# SCH_mgts_main_board_2026-06-15.net
KiCad netlist of a schematic drawn in EasyEDA
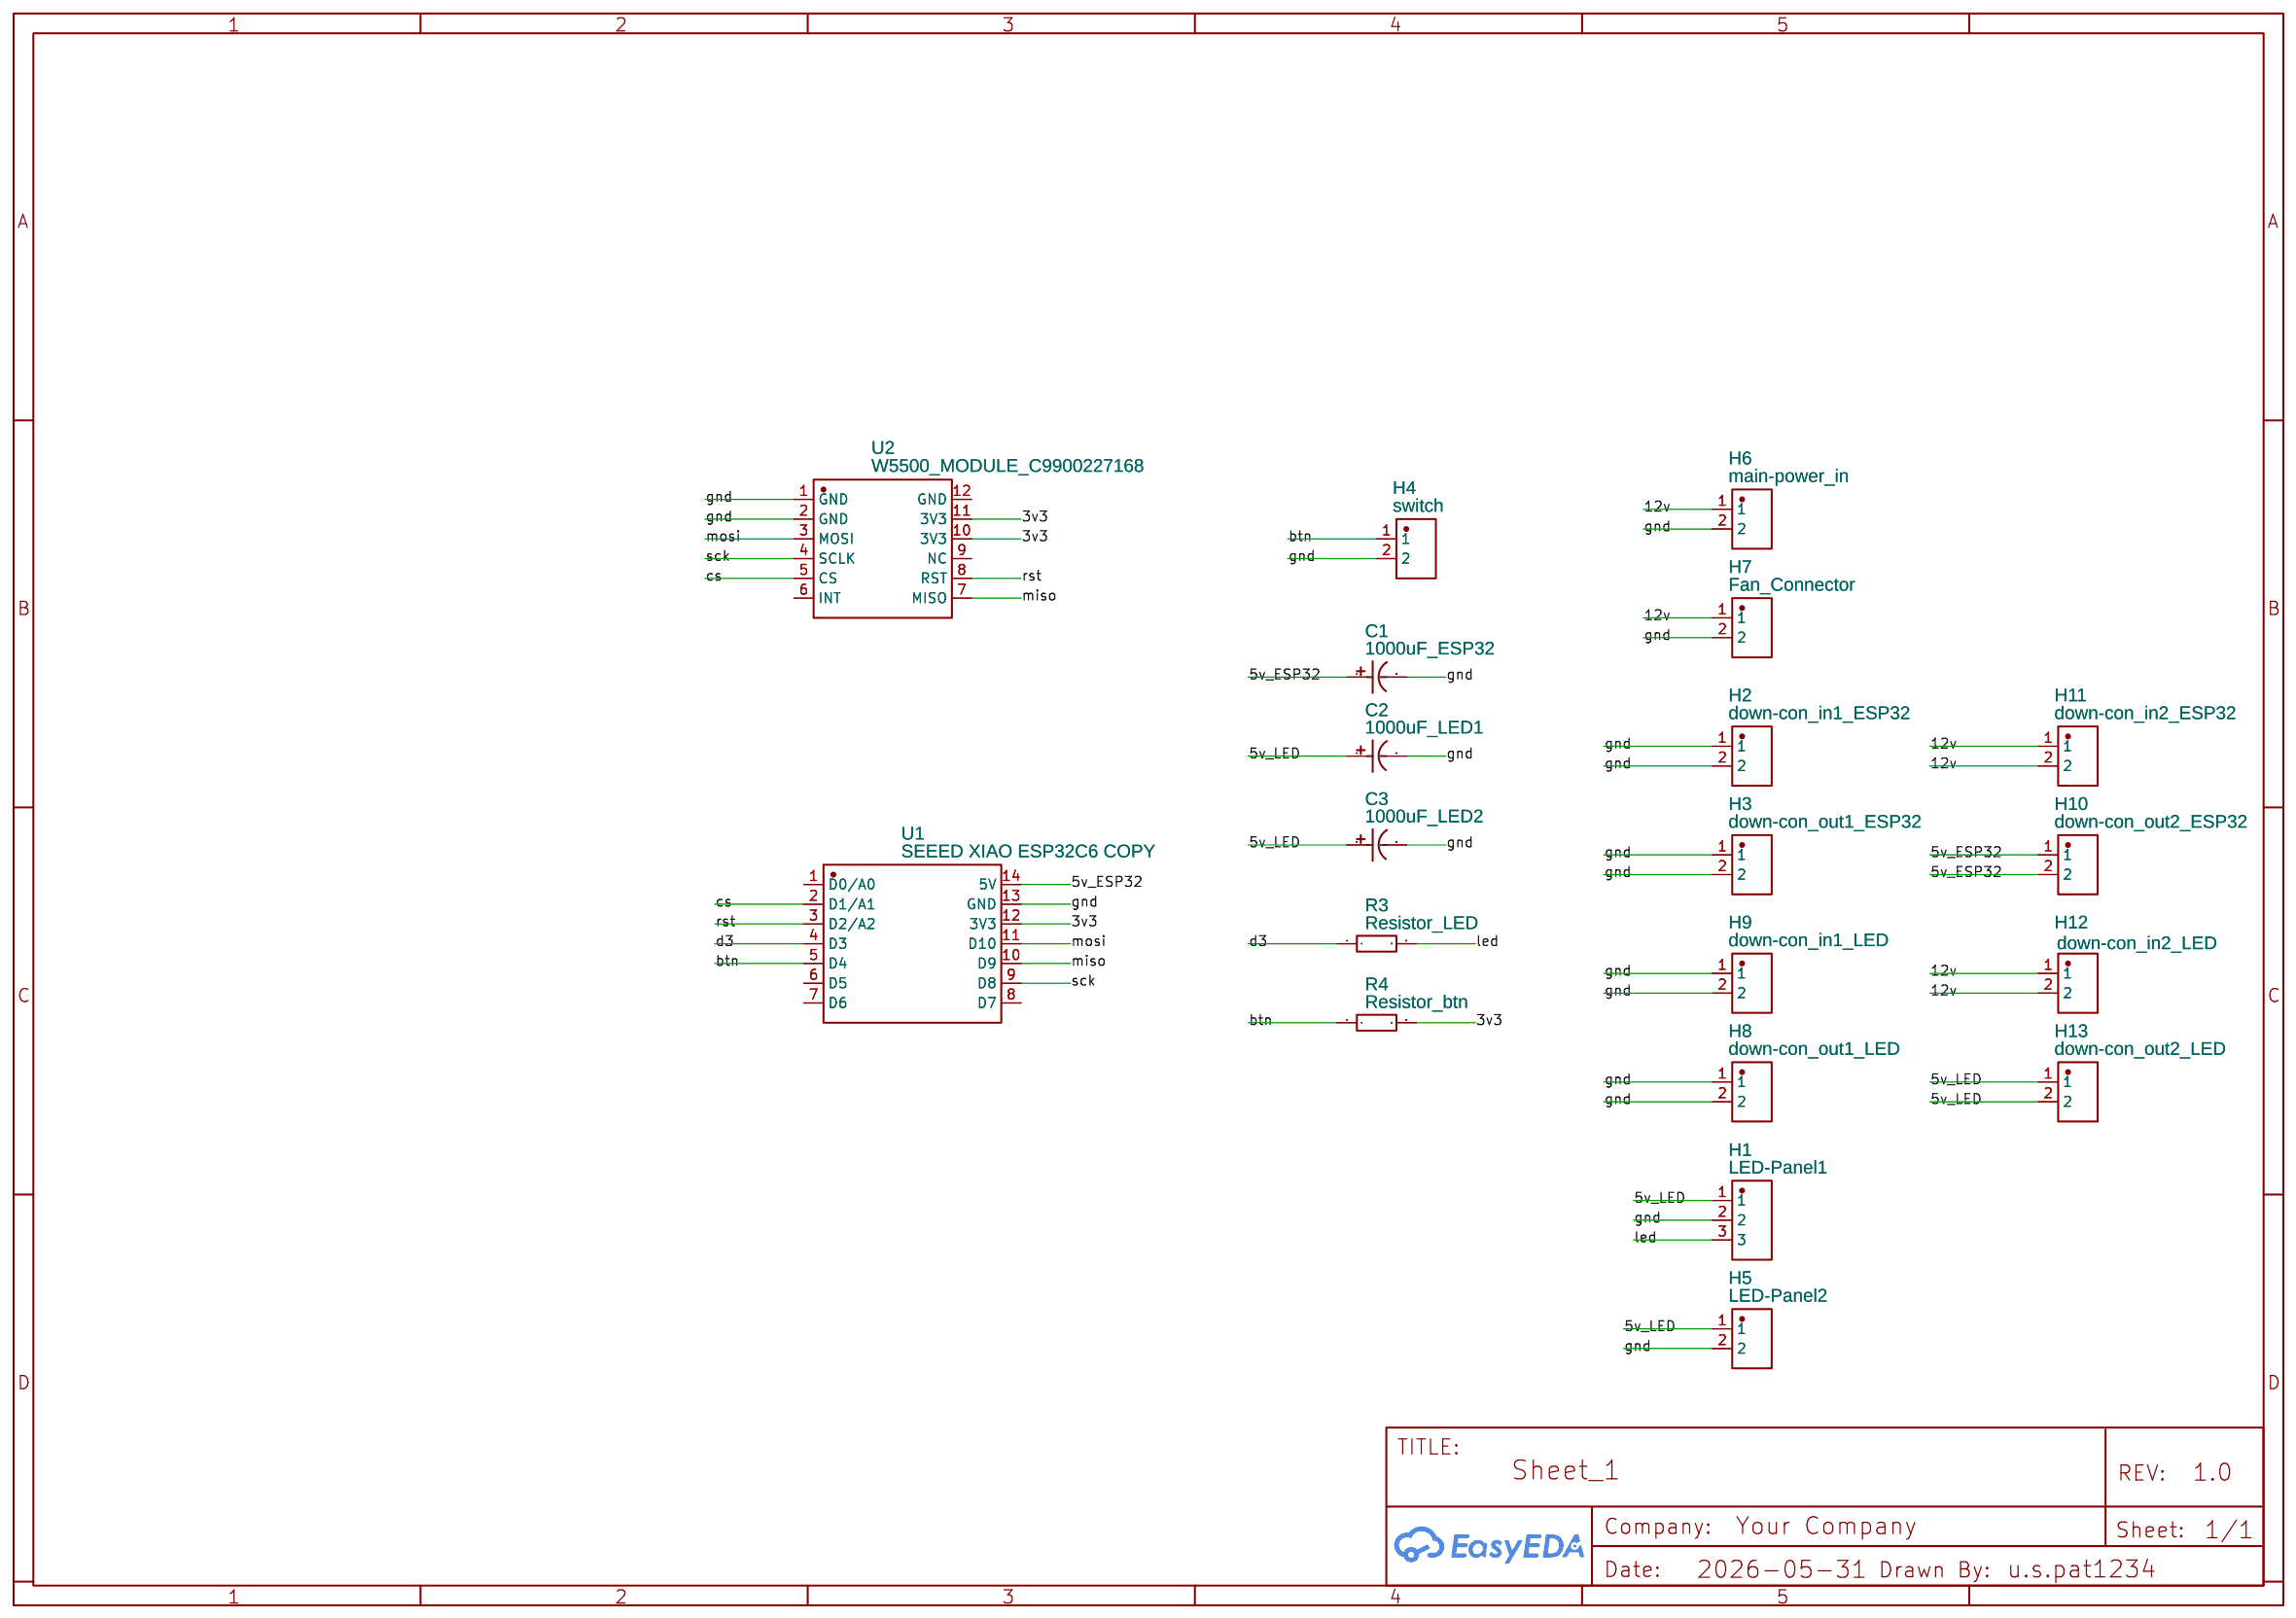
[diagram p0: schematic sheet]

(export (version "E")
  (design (tool "Eeschema 10.0.6"))
  (components
    (comp (ref "C1")
      (value "1000uF_ESP32")
      (fields (field (name "Manufacturer Part") "1000uF"))
      (libsource (lib "") (part "1000uF"))
    )
    (comp (ref "C2")
      (value "1000uF_LED1")
      (fields (field (name "Manufacturer Part") "1000uF"))
      (libsource (lib "") (part "1000uF"))
    )
    (comp (ref "C3")
      (value "1000uF_LED2")
      (fields (field (name "Manufacturer Part") "1000uF"))
      (libsource (lib "") (part "1000uF"))
    )
    (comp (ref "H1")
      (value "LED-Panel1")
      (fields (field (name "Manufacturer Part") "XY-2.54-1*3PZ") (field (name "Manufacturer") "XYECONN(辛译)"))
      (libsource (lib "") (part "XY-2.54-1*3PZ"))
    )
    (comp (ref "H2")
      (value "down-con_in1_ESP32")
      (fields
        (field (name "Manufacturer Part") "KH-2.54PH90-1X2P-L13.8")
        (field (name "Manufacturer") "kinghelm(金航标)")
      )
      (libsource (lib "") (part "KH-2.54PH90-1X2P-L13.8"))
    )
    (comp (ref "H3")
      (value "down-con_out1_ESP32")
      (fields
        (field (name "Manufacturer Part") "KH-2.54PH90-1X2P-L13.8")
        (field (name "Manufacturer") "kinghelm(金航标)")
      )
      (libsource (lib "") (part "KH-2.54PH90-1X2P-L13.8"))
    )
    (comp (ref "H4")
      (value "switch")
      (fields
        (field (name "Manufacturer Part") "KH-2.54PH90-1X2P-L13.8")
        (field (name "Manufacturer") "kinghelm(金航标)")
      )
      (libsource (lib "") (part "KH-2.54PH90-1X2P-L13.8"))
    )
    (comp (ref "H5")
      (value "LED-Panel2")
      (fields
        (field (name "Manufacturer Part") "KH-2.54PH90-1X2P-L13.8")
        (field (name "Manufacturer") "kinghelm(金航标)")
      )
      (libsource (lib "") (part "KH-2.54PH90-1X2P-L13.8"))
    )
    (comp (ref "H6")
      (value "main-power_in")
      (fields
        (field (name "Manufacturer Part") "KH-2.54PH90-1X2P-L13.8")
        (field (name "Manufacturer") "kinghelm(金航标)")
      )
      (libsource (lib "") (part "KH-2.54PH90-1X2P-L13.8"))
    )
    (comp (ref "H7")
      (value "Fan_Connector")
      (fields
        (field (name "Manufacturer Part") "KH-2.54PH90-1X2P-L13.8")
        (field (name "Manufacturer") "kinghelm(金航标)")
      )
      (libsource (lib "") (part "KH-2.54PH90-1X2P-L13.8"))
    )
    (comp (ref "H8")
      (value "down-con_out1_LED")
      (fields
        (field (name "Manufacturer Part") "KH-2.54PH90-1X2P-L13.8")
        (field (name "Manufacturer") "kinghelm(金航标)")
      )
      (libsource (lib "") (part "KH-2.54PH90-1X2P-L13.8"))
    )
    (comp (ref "H9")
      (value "down-con_in1_LED")
      (fields
        (field (name "Manufacturer Part") "KH-2.54PH90-1X2P-L13.8")
        (field (name "Manufacturer") "kinghelm(金航标)")
      )
      (libsource (lib "") (part "KH-2.54PH90-1X2P-L13.8"))
    )
    (comp (ref "H10")
      (value "down-con_out2_ESP32")
      (fields
        (field (name "Manufacturer Part") "KH-2.54PH90-1X2P-L13.8")
        (field (name "Manufacturer") "kinghelm(金航标)")
      )
      (libsource (lib "") (part "KH-2.54PH90-1X2P-L13.8"))
    )
    (comp (ref "H11")
      (value "down-con_in2_ESP32")
      (fields
        (field (name "Manufacturer Part") "KH-2.54PH90-1X2P-L13.8")
        (field (name "Manufacturer") "kinghelm(金航标)")
      )
      (libsource (lib "") (part "KH-2.54PH90-1X2P-L13.8"))
    )
    (comp (ref "H12")
      (value "down-con_in2_LED")
      (fields
        (field (name "Manufacturer Part") "KH-2.54PH90-1X2P-L13.8")
        (field (name "Manufacturer") "kinghelm(金航标)")
      )
      (libsource (lib "") (part "KH-2.54PH90-1X2P-L13.8"))
    )
    (comp (ref "H13")
      (value "down-con_out2_LED")
      (fields
        (field (name "Manufacturer Part") "KH-2.54PH90-1X2P-L13.8")
        (field (name "Manufacturer") "kinghelm(金航标)")
      )
      (libsource (lib "") (part "KH-2.54PH90-1X2P-L13.8"))
    )
    (comp (ref "R3")
      (value "Resistor_LED")
      (fields (field (name "Manufacturer Part") "1K-AXIAL-0.4"))
      (libsource (lib "") (part "1K-AXIAL-0.4"))
    )
    (comp (ref "R4")
      (value "Resistor_btn")
      (fields (field (name "Manufacturer Part") "1K-AXIAL-0.4"))
      (libsource (lib "") (part "1K-AXIAL-0.4"))
    )
    (comp (ref "U1")
      (value "SEEED XIAO ESP32C6 COPY")
      (fields (field (name "Manufacturer Part") "XIAO ESP32C6") (field (name "Manufacturer") "Seeed Studio"))
      (libsource (lib "") (part "SEEED XIAO ESP32C6 COPY"))
    )
    (comp (ref "U2")
      (value "W5500_MODULE_C9900227168")
      (fields (field (name "Manufacturer Part") "W5500_MODULE"))
      (libsource (lib "") (part "W5500_MODULE_C9900227168"))
    )
  )
  (nets
    (net (code "1") (name "/3v3") (class "Default")
      (node (ref "R4") (pin "2") (pinfunction "2_2") (pintype "unspecified"))
      (node (ref "U1") (pin "12") (pinfunction "3V3_12") (pintype "unspecified"))
      (node (ref "U2") (pin "10") (pinfunction "3V3_10") (pintype "unspecified"))
      (node (ref "U2") (pin "11") (pinfunction "3V3_11") (pintype "unspecified"))
    )
    (net (code "2") (name "/5v_ESP32") (class "Default")
      (node (ref "C1") (pin "1") (pinfunction "1_1") (pintype "input"))
      (node (ref "H10") (pin "1") (pinfunction "1_1") (pintype "unspecified"))
      (node (ref "H10") (pin "2") (pinfunction "2_2") (pintype "unspecified"))
      (node (ref "U1") (pin "14") (pinfunction "5V_14") (pintype "unspecified"))
    )
    (net (code "3") (name "/5v_LED") (class "Default")
      (node (ref "C2") (pin "1") (pinfunction "1_1") (pintype "input"))
      (node (ref "C3") (pin "1") (pinfunction "1_1") (pintype "input"))
      (node (ref "H1") (pin "1") (pinfunction "1_1") (pintype "unspecified"))
      (node (ref "H13") (pin "1") (pinfunction "1_1") (pintype "unspecified"))
      (node (ref "H13") (pin "2") (pinfunction "2_2") (pintype "unspecified"))
      (node (ref "H5") (pin "1") (pinfunction "1_1") (pintype "unspecified"))
    )
    (net (code "4") (name "/12v") (class "Default")
      (node (ref "H11") (pin "1") (pinfunction "1_1") (pintype "unspecified"))
      (node (ref "H11") (pin "2") (pinfunction "2_2") (pintype "unspecified"))
      (node (ref "H12") (pin "1") (pinfunction "1_1") (pintype "unspecified"))
      (node (ref "H12") (pin "2") (pinfunction "2_2") (pintype "unspecified"))
      (node (ref "H6") (pin "1") (pinfunction "1_1") (pintype "unspecified"))
      (node (ref "H7") (pin "1") (pinfunction "1_1") (pintype "unspecified"))
    )
    (net (code "5") (name "/btn") (class "Default")
      (node (ref "H4") (pin "1") (pinfunction "1_1") (pintype "unspecified"))
      (node (ref "R4") (pin "1") (pinfunction "1_1") (pintype "unspecified"))
      (node (ref "U1") (pin "5") (pinfunction "D4_5") (pintype "unspecified"))
    )
    (net (code "6") (name "/cs") (class "Default")
      (node (ref "U1") (pin "2") (pinfunction "D1/A1_2") (pintype "unspecified"))
      (node (ref "U2") (pin "5") (pinfunction "CS_5") (pintype "unspecified"))
    )
    (net (code "7") (name "/d3") (class "Default")
      (node (ref "R3") (pin "1") (pinfunction "1_1") (pintype "unspecified"))
      (node (ref "U1") (pin "4") (pinfunction "D3_4") (pintype "unspecified"))
    )
    (net (code "8") (name "/gnd") (class "Default")
      (node (ref "C1") (pin "2") (pinfunction "2_2") (pintype "input"))
      (node (ref "C2") (pin "2") (pinfunction "2_2") (pintype "input"))
      (node (ref "C3") (pin "2") (pinfunction "2_2") (pintype "input"))
      (node (ref "H1") (pin "2") (pinfunction "2_2") (pintype "unspecified"))
      (node (ref "H2") (pin "1") (pinfunction "1_1") (pintype "unspecified"))
      (node (ref "H2") (pin "2") (pinfunction "2_2") (pintype "unspecified"))
      (node (ref "H3") (pin "1") (pinfunction "1_1") (pintype "unspecified"))
      (node (ref "H3") (pin "2") (pinfunction "2_2") (pintype "unspecified"))
      (node (ref "H4") (pin "2") (pinfunction "2_2") (pintype "unspecified"))
      (node (ref "H5") (pin "2") (pinfunction "2_2") (pintype "unspecified"))
      (node (ref "H6") (pin "2") (pinfunction "2_2") (pintype "unspecified"))
      (node (ref "H7") (pin "2") (pinfunction "2_2") (pintype "unspecified"))
      (node (ref "H8") (pin "1") (pinfunction "1_1") (pintype "unspecified"))
      (node (ref "H8") (pin "2") (pinfunction "2_2") (pintype "unspecified"))
      (node (ref "H9") (pin "1") (pinfunction "1_1") (pintype "unspecified"))
      (node (ref "H9") (pin "2") (pinfunction "2_2") (pintype "unspecified"))
      (node (ref "U1") (pin "13") (pinfunction "GND_13") (pintype "unspecified"))
      (node (ref "U2") (pin "1") (pinfunction "GND_1") (pintype "unspecified"))
      (node (ref "U2") (pin "2") (pinfunction "GND_2") (pintype "unspecified"))
    )
    (net (code "9") (name "/led") (class "Default")
      (node (ref "H1") (pin "3") (pinfunction "3_3") (pintype "unspecified"))
      (node (ref "R3") (pin "2") (pinfunction "2_2") (pintype "unspecified"))
    )
    (net (code "10") (name "/miso") (class "Default")
      (node (ref "U1") (pin "10") (pinfunction "D9_10") (pintype "unspecified"))
      (node (ref "U2") (pin "7") (pinfunction "MISO_7") (pintype "unspecified"))
    )
    (net (code "11") (name "/mosi") (class "Default")
      (node (ref "U1") (pin "11") (pinfunction "D10_11") (pintype "unspecified"))
      (node (ref "U2") (pin "3") (pinfunction "MOSI_3") (pintype "unspecified"))
    )
    (net (code "12") (name "/rst") (class "Default")
      (node (ref "U1") (pin "3") (pinfunction "D2/A2_3") (pintype "unspecified"))
      (node (ref "U2") (pin "8") (pinfunction "RST_8") (pintype "unspecified"))
    )
    (net (code "13") (name "/sck") (class "Default")
      (node (ref "U1") (pin "9") (pinfunction "D8_9") (pintype "unspecified"))
      (node (ref "U2") (pin "4") (pinfunction "SCLK_4") (pintype "unspecified"))
    )
    (net (code "14") (name "unconnected-(U1-D0{slash}A0-Pad1)") (class "Default")
      (node (ref "U1") (pin "1") (pinfunction "D0/A0_1") (pintype "unspecified"))
    )
    (net (code "15") (name "unconnected-(U1-D5-Pad6)") (class "Default")
      (node (ref "U1") (pin "6") (pinfunction "D5_6") (pintype "unspecified"))
    )
    (net (code "16") (name "unconnected-(U1-D6-Pad7)") (class "Default")
      (node (ref "U1") (pin "7") (pinfunction "D6_7") (pintype "unspecified"))
    )
    (net (code "17") (name "unconnected-(U1-D7-Pad8)") (class "Default")
      (node (ref "U1") (pin "8") (pinfunction "D7_8") (pintype "unspecified"))
    )
    (net (code "18") (name "unconnected-(U2-GND-Pad12)") (class "Default")
      (node (ref "U2") (pin "12") (pinfunction "GND_12") (pintype "unspecified"))
    )
    (net (code "19") (name "unconnected-(U2-INT-Pad6)") (class "Default")
      (node (ref "U2") (pin "6") (pinfunction "INT_6") (pintype "unspecified"))
    )
    (net (code "20") (name "unconnected-(U2-NC-Pad9)") (class "Default")
      (node (ref "U2") (pin "9") (pinfunction "NC_9") (pintype "unspecified"))
    )
  )
)
